# portalhub.net
KiCad netlist of a schematic drawn in EasyEDA Pro
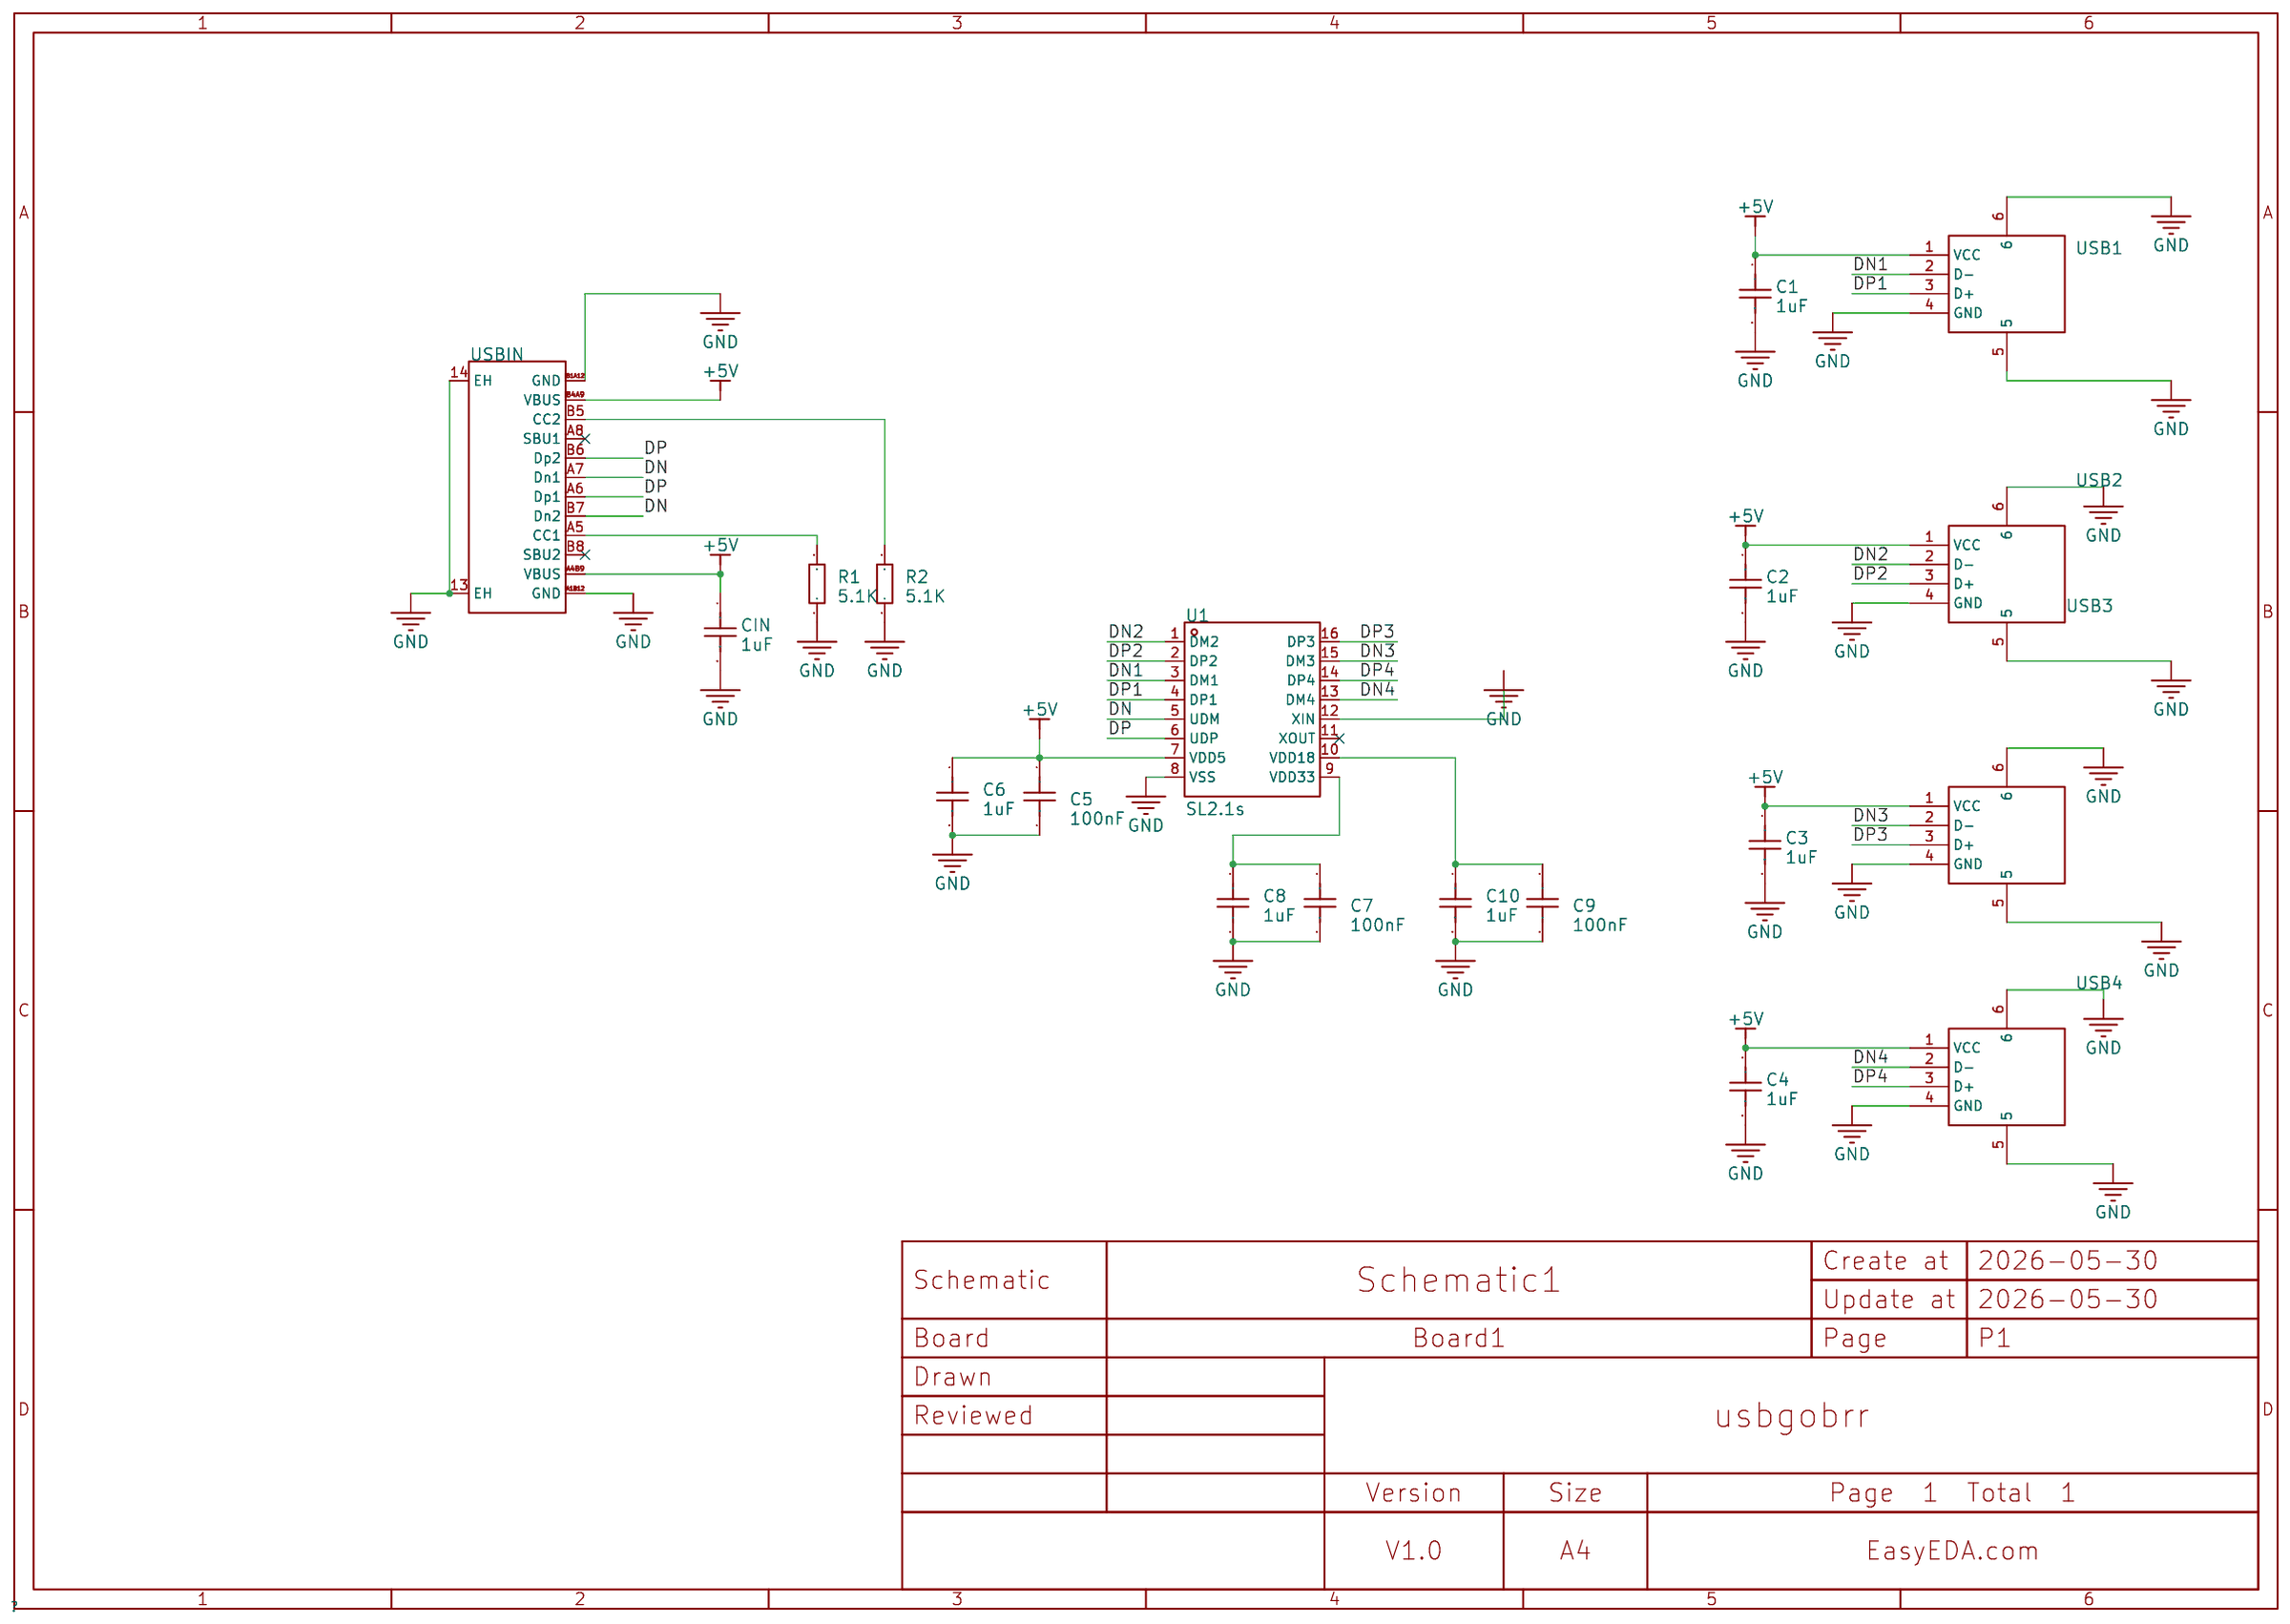
[diagram p0: schematic sheet]

(export (version "E")
  (design (tool "Eeschema 10.0.6"))
  (components
    (comp (ref "C1") (value "1uF") (footprint "easyedapro:C0603") (libsource (lib "easyedapro") (part "CAP")))
    (comp (ref "C2") (value "1uF") (footprint "easyedapro:C0603") (libsource (lib "easyedapro") (part "CAP")))
    (comp (ref "C3") (value "1uF") (footprint "easyedapro:C0603") (libsource (lib "easyedapro") (part "CAP")))
    (comp (ref "C4") (value "1uF") (footprint "easyedapro:C0603") (libsource (lib "easyedapro") (part "CAP")))
    (comp (ref "C5")
      (value "100nF")
      (footprint "easyedapro:C0603")
      (libsource (lib "easyedapro") (part "CAP"))
    )
    (comp (ref "C6") (value "1uF") (footprint "easyedapro:C0603") (libsource (lib "easyedapro") (part "CAP")))
    (comp (ref "C7")
      (value "100nF")
      (footprint "easyedapro:C0603")
      (libsource (lib "easyedapro") (part "CAP"))
    )
    (comp (ref "C8") (value "1uF") (footprint "easyedapro:C0603") (libsource (lib "easyedapro") (part "CAP")))
    (comp (ref "C9")
      (value "100nF")
      (footprint "easyedapro:C0603")
      (libsource (lib "easyedapro") (part "CAP"))
    )
    (comp (ref "C10")
      (value "1uF")
      (footprint "easyedapro:C0603")
      (libsource (lib "easyedapro") (part "CAP"))
    )
    (comp (ref "CIN")
      (value "1uF")
      (footprint "easyedapro:C0603")
      (libsource (lib "easyedapro") (part "CAP"))
    )
    (comp (ref "R1")
      (value "5.1K")
      (footprint "easyedapro:R0603")
      (libsource (lib "easyedapro") (part "Res"))
    )
    (comp (ref "R2")
      (value "5.1K")
      (footprint "easyedapro:R0603")
      (libsource (lib "easyedapro") (part "Res"))
    )
    (comp (ref "U1")
      (value "SL2.1s")
      (footprint "easyedapro:SSOP-16_L4.6-W2.6-P0.53-LS4.0-BL")
      (fields (field (name "Manufacturer") "CoreChips(和芯润德)"))
      (libsource (lib "easyedapro") (part "SL2.1S"))
    )
    (comp (ref "USB1")
      (value "10.0 QHHTZB6.3")
      (footprint "easyedapro:USB-A-TH_10.0QHHTZB6.3")
      (fields (field (name "Manufacturer") "SHOU HAN(首韩)"))
      (libsource (lib "easyedapro") (part "10.0 QHHTZB6.3"))
    )
    (comp (ref "USB2")
      (value "10.0 QHHTZB6.3")
      (footprint "easyedapro:USB-A-TH_10.0QHHTZB6.3")
      (fields (field (name "Manufacturer") "SHOU HAN(首韩)"))
      (libsource (lib "easyedapro") (part "10.0 QHHTZB6.3"))
    )
    (comp (ref "USB3")
      (value "10.0 QHHTZB6.3")
      (footprint "easyedapro:USB-A-TH_10.0QHHTZB6.3")
      (fields (field (name "Manufacturer") "SHOU HAN(首韩)"))
      (libsource (lib "easyedapro") (part "10.0 QHHTZB6.3"))
    )
    (comp (ref "USB4")
      (value "10.0 QHHTZB6.3")
      (footprint "easyedapro:USB-A-TH_10.0QHHTZB6.3")
      (fields (field (name "Manufacturer") "SHOU HAN(首韩)"))
      (libsource (lib "easyedapro") (part "10.0 QHHTZB6.3"))
    )
    (comp (ref "USBIN")
      (value "TYPE-C 16PIN 2MD(073)")
      (footprint "easyedapro:USB-C-SMD_TYPE-C-16PIN-2MD-073")
      (fields (field (name "Manufacturer") "SHOU HAN(首韩)"))
      (libsource (lib "easyedapro") (part "TYPE-C 16PIN 2MD(073)"))
    )
  )
  (nets
    (net (code "1") (name "+5V") (class "Default")
      (node (ref "C1") (pin "1") (pinfunction "1_1") (pintype "input"))
      (node (ref "C2") (pin "1") (pinfunction "1_1") (pintype "input"))
      (node (ref "C3") (pin "1") (pinfunction "1_1") (pintype "input"))
      (node (ref "C4") (pin "1") (pinfunction "1_1") (pintype "input"))
      (node (ref "C5") (pin "1") (pinfunction "1_1") (pintype "input"))
      (node (ref "C6") (pin "1") (pinfunction "1_1") (pintype "input"))
      (node (ref "CIN") (pin "1") (pinfunction "1_1") (pintype "input"))
      (node (ref "U1") (pin "7") (pinfunction "VDD5_7") (pintype "unspecified"))
      (node (ref "USB1") (pin "1") (pinfunction "VCC_1") (pintype "unspecified"))
      (node (ref "USB2") (pin "1") (pinfunction "VCC_1") (pintype "unspecified"))
      (node (ref "USB3") (pin "1") (pinfunction "VCC_1") (pintype "unspecified"))
      (node (ref "USB4") (pin "1") (pinfunction "VCC_1") (pintype "unspecified"))
      (node (ref "USBIN") (pin "A4B9") (pinfunction "VBUS_A4B9") (pintype "unspecified"))
      (node (ref "USBIN") (pin "B4A9") (pinfunction "VBUS_B4A9") (pintype "unspecified"))
    )
    (net (code "2") (name "/DN") (class "Default")
      (node (ref "U1") (pin "5") (pinfunction "UDM_5") (pintype "unspecified"))
      (node (ref "USBIN") (pin "A7") (pinfunction "Dn1_A7") (pintype "unspecified"))
      (node (ref "USBIN") (pin "B7") (pinfunction "Dn2_B7") (pintype "unspecified"))
    )
    (net (code "3") (name "/DN1") (class "Default")
      (node (ref "U1") (pin "3") (pinfunction "DM1_3") (pintype "unspecified"))
      (node (ref "USB1") (pin "2") (pinfunction "D-_2") (pintype "unspecified"))
    )
    (net (code "4") (name "/DN2") (class "Default")
      (node (ref "U1") (pin "1") (pinfunction "DM2_1") (pintype "unspecified"))
      (node (ref "USB2") (pin "2") (pinfunction "D-_2") (pintype "unspecified"))
    )
    (net (code "5") (name "/DN3") (class "Default")
      (node (ref "U1") (pin "15") (pinfunction "DM3_15") (pintype "unspecified"))
      (node (ref "USB3") (pin "2") (pinfunction "D-_2") (pintype "unspecified"))
    )
    (net (code "6") (name "/DN4") (class "Default")
      (node (ref "U1") (pin "13") (pinfunction "DM4_13") (pintype "unspecified"))
      (node (ref "USB4") (pin "2") (pinfunction "D-_2") (pintype "unspecified"))
    )
    (net (code "7") (name "/DP") (class "Default")
      (node (ref "U1") (pin "6") (pinfunction "UDP_6") (pintype "unspecified"))
      (node (ref "USBIN") (pin "A6") (pinfunction "Dp1_A6") (pintype "unspecified"))
      (node (ref "USBIN") (pin "B6") (pinfunction "Dp2_B6") (pintype "unspecified"))
    )
    (net (code "8") (name "/DP1") (class "Default")
      (node (ref "U1") (pin "4") (pinfunction "DP1_4") (pintype "unspecified"))
      (node (ref "USB1") (pin "3") (pinfunction "D+_3") (pintype "unspecified"))
    )
    (net (code "9") (name "/DP2") (class "Default")
      (node (ref "U1") (pin "2") (pinfunction "DP2_2") (pintype "unspecified"))
      (node (ref "USB2") (pin "3") (pinfunction "D+_3") (pintype "unspecified"))
    )
    (net (code "10") (name "/DP3") (class "Default")
      (node (ref "U1") (pin "16") (pinfunction "DP3_16") (pintype "unspecified"))
      (node (ref "USB3") (pin "3") (pinfunction "D+_3") (pintype "unspecified"))
    )
    (net (code "11") (name "/DP4") (class "Default")
      (node (ref "U1") (pin "14") (pinfunction "DP4_14") (pintype "unspecified"))
      (node (ref "USB4") (pin "3") (pinfunction "D+_3") (pintype "unspecified"))
    )
    (net (code "12") (name "GND") (class "Default")
      (node (ref "C1") (pin "2") (pinfunction "2_2") (pintype "input"))
      (node (ref "C10") (pin "2") (pinfunction "2_2") (pintype "input"))
      (node (ref "C2") (pin "2") (pinfunction "2_2") (pintype "input"))
      (node (ref "C3") (pin "2") (pinfunction "2_2") (pintype "input"))
      (node (ref "C4") (pin "2") (pinfunction "2_2") (pintype "input"))
      (node (ref "C5") (pin "2") (pinfunction "2_2") (pintype "input"))
      (node (ref "C6") (pin "2") (pinfunction "2_2") (pintype "input"))
      (node (ref "C7") (pin "2") (pinfunction "2_2") (pintype "input"))
      (node (ref "C8") (pin "2") (pinfunction "2_2") (pintype "input"))
      (node (ref "C9") (pin "2") (pinfunction "2_2") (pintype "input"))
      (node (ref "CIN") (pin "2") (pinfunction "2_2") (pintype "input"))
      (node (ref "R1") (pin "1") (pinfunction "1_1") (pintype "input"))
      (node (ref "R2") (pin "1") (pinfunction "1_1") (pintype "input"))
      (node (ref "U1") (pin "12") (pinfunction "XIN_12") (pintype "unspecified"))
      (node (ref "U1") (pin "8") (pinfunction "VSS_8") (pintype "unspecified"))
      (node (ref "USB1") (pin "4") (pinfunction "GND_4") (pintype "unspecified"))
      (node (ref "USB1") (pin "5") (pinfunction "5_5") (pintype "unspecified"))
      (node (ref "USB1") (pin "6") (pinfunction "6_6") (pintype "unspecified"))
      (node (ref "USB2") (pin "4") (pinfunction "GND_4") (pintype "unspecified"))
      (node (ref "USB2") (pin "5") (pinfunction "5_5") (pintype "unspecified"))
      (node (ref "USB2") (pin "6") (pinfunction "6_6") (pintype "unspecified"))
      (node (ref "USB3") (pin "4") (pinfunction "GND_4") (pintype "unspecified"))
      (node (ref "USB3") (pin "5") (pinfunction "5_5") (pintype "unspecified"))
      (node (ref "USB3") (pin "6") (pinfunction "6_6") (pintype "unspecified"))
      (node (ref "USB4") (pin "4") (pinfunction "GND_4") (pintype "unspecified"))
      (node (ref "USB4") (pin "5") (pinfunction "5_5") (pintype "unspecified"))
      (node (ref "USB4") (pin "6") (pinfunction "6_6") (pintype "unspecified"))
      (node (ref "USBIN") (pin "13") (pinfunction "EH_13") (pintype "unspecified"))
      (node (ref "USBIN") (pin "14") (pinfunction "EH_14") (pintype "unspecified"))
      (node (ref "USBIN") (pin "A1B12") (pinfunction "GND_A1B12") (pintype "unspecified"))
      (node (ref "USBIN") (pin "B1A12") (pinfunction "GND_B1A12") (pintype "unspecified"))
    )
    (net (code "13") (name "Net-(U1-VDD18)") (class "Default")
      (node (ref "C10") (pin "1") (pinfunction "1_1") (pintype "input"))
      (node (ref "C9") (pin "1") (pinfunction "1_1") (pintype "input"))
      (node (ref "U1") (pin "10") (pinfunction "VDD18_10") (pintype "unspecified"))
    )
    (net (code "14") (name "Net-(U1-VDD33)") (class "Default")
      (node (ref "C7") (pin "1") (pinfunction "1_1") (pintype "input"))
      (node (ref "C8") (pin "1") (pinfunction "1_1") (pintype "input"))
      (node (ref "U1") (pin "9") (pinfunction "VDD33_9") (pintype "unspecified"))
    )
    (net (code "15") (name "Net-(USBIN-CC1)") (class "Default")
      (node (ref "R1") (pin "2") (pinfunction "2_2") (pintype "input"))
      (node (ref "USBIN") (pin "A5") (pinfunction "CC1_A5") (pintype "unspecified"))
    )
    (net (code "16") (name "Net-(USBIN-CC2)") (class "Default")
      (node (ref "R2") (pin "2") (pinfunction "2_2") (pintype "input"))
      (node (ref "USBIN") (pin "B5") (pinfunction "CC2_B5") (pintype "unspecified"))
    )
    (net (code "17") (name "unconnected-(U1-XOUT-Pad11)") (class "Default")
      (node (ref "U1") (pin "11") (pinfunction "XOUT_11") (pintype "unspecified+no_connect"))
    )
    (net (code "18") (name "unconnected-(USBIN-SBU1-PadA8)") (class "Default")
      (node (ref "USBIN") (pin "A8") (pinfunction "SBU1_A8") (pintype "unspecified+no_connect"))
    )
    (net (code "19") (name "unconnected-(USBIN-SBU2-PadB8)") (class "Default")
      (node (ref "USBIN") (pin "B8") (pinfunction "SBU2_B8") (pintype "unspecified+no_connect"))
    )
  )
)
